# controller.net
KiCad netlist of a schematic drawn in EAGLE
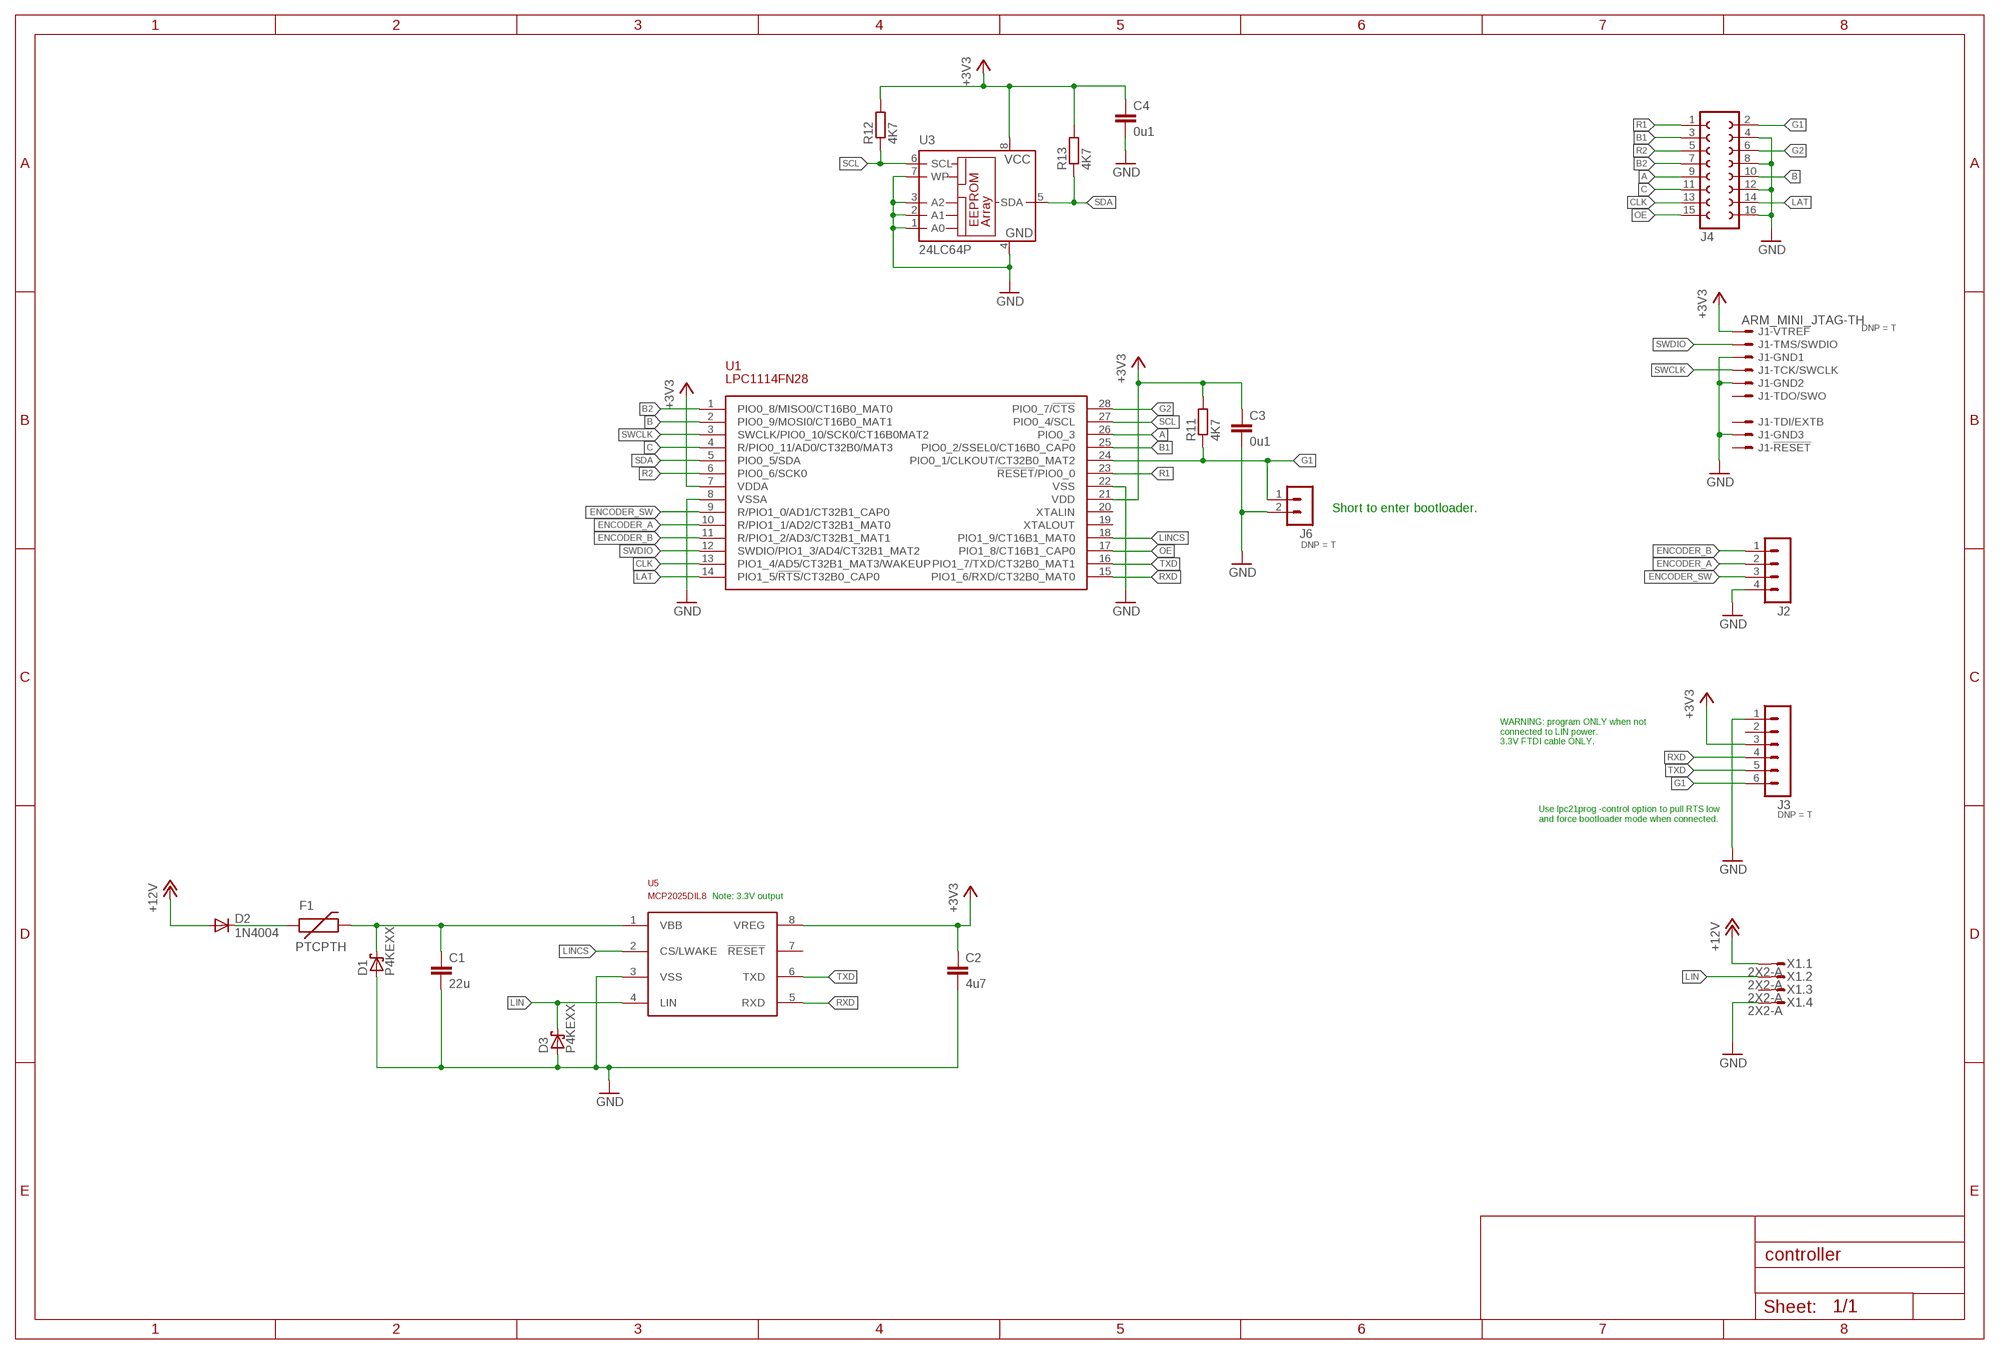
[diagram p0: schematic, sheet 1]

(export (version "E")
  (design (tool "Eeschema 10.0.6"))
  (components
    (comp (ref "C1")
      (value "22u")
      (footprint "eagle-import:C050-024X044")
      (fields (field (name "PARTNO") "FK22X5R1E226M"))
      (libsource (lib "eagle-import") (part "C-EU050-024X044"))
    )
    (comp (ref "C2")
      (value "4u7")
      (footprint "eagle-import:C050-024X044")
      (fields (field (name "PARTNO") "FK28X5R0J475K"))
      (libsource (lib "eagle-import") (part "C-EU050-024X044"))
    )
    (comp (ref "C3")
      (value "0u1")
      (footprint "eagle-import:C050-024X044")
      (fields (field (name "PARTNO") "FK28X7R1H104K"))
      (libsource (lib "eagle-import") (part "C-EU050-024X044"))
    )
    (comp (ref "C4")
      (value "0u1")
      (footprint "eagle-import:C050-024X044")
      (fields (field (name "PARTNO") "FK28X7R1H104K"))
      (libsource (lib "eagle-import") (part "C-EU050-024X044"))
    )
    (comp (ref "D1")
      (value "P4KEXX")
      (footprint "eagle-import:DO41-10")
      (fields (field (name "PARTNO") "P4KE30CA"))
      (libsource (lib "eagle-import") (part "P4KEXX"))
    )
    (comp (ref "D2")
      (value "1N4004")
      (footprint "eagle-import:DO41-10")
      (fields (field (name "PARTNO") "1N4004-TP"))
      (libsource (lib "eagle-import") (part "1N4004"))
    )
    (comp (ref "D3")
      (value "P4KEXX")
      (footprint "eagle-import:DO41-10")
      (fields (field (name "PARTNO") "P4KE30CA"))
      (libsource (lib "eagle-import") (part "P4KEXX"))
    )
    (comp (ref "F1")
      (value "PTCPTH")
      (footprint "eagle-import:PTC")
      (fields (field (name "PARTNO") "CMF-RL10-0"))
      (libsource (lib "eagle-import") (part "PTCPTH"))
    )
    (comp (ref "J1")
      (value "ARM_MINI_JTAG-TH")
      (footprint "eagle-import:FTSH-105-01-XXX-DV")
      (fields (field (name "DNP") "T") (field (name "PARTNO") "*"))
      (libsource (lib "eagle-import") (part "ARM_MINI_JTAG-TH"))
    )
    (comp (ref "J2")
      (value "MA04-1")
      (footprint "eagle-import:MA04-1")
      (fields (field (name "PARTNO") "640454-4"))
      (libsource (lib "eagle-import") (part "MA04-1"))
    )
    (comp (ref "J3")
      (value "MA06-1")
      (footprint "eagle-import:MA06-1")
      (fields (field (name "DNP") "T"))
      (libsource (lib "eagle-import") (part "MA06-1"))
    )
    (comp (ref "J4")
      (value "FE08-2")
      (footprint "eagle-import:FE08-2")
      (fields (field (name "PARTNO") "PPTC082LFBN-RC"))
      (libsource (lib "eagle-import") (part "FE08-2"))
    )
    (comp (ref "J6")
      (value "MA02-1Y")
      (footprint "eagle-import:MA02-1Y")
      (fields (field (name "DNP") "T"))
      (libsource (lib "eagle-import") (part "MA02-1Y"))
    )
    (comp (ref "R11")
      (value "4K7")
      (footprint "eagle-import:0207_10")
      (fields (field (name "PARTNO") "MFR-25FBF52-4K99"))
      (libsource (lib "eagle-import") (part "R-EU_0207/10"))
    )
    (comp (ref "R12")
      (value "4K7")
      (footprint "eagle-import:0207_10")
      (fields (field (name "PARTNO") "MFR-25FBF52-4K99"))
      (libsource (lib "eagle-import") (part "R-EU_0207/10"))
    )
    (comp (ref "R13")
      (value "4K7")
      (footprint "eagle-import:0207_10")
      (fields (field (name "PARTNO") "MFR-25FBF52-4K99"))
      (libsource (lib "eagle-import") (part "R-EU_0207/10"))
    )
    (comp (ref "U1")
      (value "LPC1114FN28")
      (footprint "eagle-import:DIL28")
      (fields (field (name "PARTNO") "LPC1114FN28/102,12"))
      (libsource (lib "eagle-import") (part "LPC1114FN28"))
    )
    (comp (ref "U3")
      (value "24LC64P")
      (footprint "eagle-import:DIL8")
      (fields (field (name "MF") "MICROCHIP") (field (name "MPN") "24LC64-I/P"))
      (libsource (lib "eagle-import") (part "24PLC64"))
    )
    (comp (ref "U5")
      (value "MCP2025DIL8")
      (footprint "eagle-import:DIL8")
      (fields (field (name "PARTNO") "MCP2025-330E/P"))
      (libsource (lib "eagle-import") (part "MCP2025DIL8"))
    )
    (comp (ref "X1")
      (value "2X2-A")
      (footprint "eagle-import:3-794618-4")
      (fields (field (name "PARTNO") "3-794618-4"))
      (libsource (lib "eagle-import") (part "2X2-A"))
    )
  )
  (nets
    (net (code "1") (name "+3V3") (class "Default")
      (node (ref "C2") (pin "1") (pinfunction "1_1") (pintype "passive"))
      (node (ref "C3") (pin "1") (pinfunction "1_1") (pintype "passive"))
      (node (ref "C4") (pin "1") (pinfunction "1_1") (pintype "passive"))
      (node (ref "J1") (pin "1") (pinfunction "S_1") (pintype "passive"))
      (node (ref "J3") (pin "3") (pinfunction "3_3") (pintype "passive"))
      (node (ref "R11") (pin "2") (pinfunction "2_2") (pintype "passive"))
      (node (ref "R12") (pin "2") (pinfunction "2_2") (pintype "passive"))
      (node (ref "R13") (pin "2") (pinfunction "2_2") (pintype "passive"))
      (node (ref "U1") (pin "21") (pinfunction "VDD_21") (pintype "power_in"))
      (node (ref "U1") (pin "7") (pinfunction "VDDA_7") (pintype "power_in"))
      (node (ref "U3") (pin "8") (pinfunction "VCC_8") (pintype "power_in"))
      (node (ref "U5") (pin "8") (pinfunction "VREG_8") (pintype "power_in"))
    )
    (net (code "2") (name "+12V") (class "Default")
      (node (ref "D2") (pin "A") (pinfunction "A_A") (pintype "passive"))
      (node (ref "X1") (pin "1") (pinfunction "S_1") (pintype "passive"))
    )
    (net (code "3") (name "A") (class "Default")
      (node (ref "J4") (pin "9") (pinfunction "9_9") (pintype "passive"))
      (node (ref "U1") (pin "26") (pinfunction "PIO0_3_26") (pintype "bidirectional"))
    )
    (net (code "4") (name "B") (class "Default")
      (node (ref "J4") (pin "10") (pinfunction "10_10") (pintype "passive"))
      (node (ref "U1") (pin "2") (pinfunction "PIO0_9/MOSI0/CT16B0_MAT1_2") (pintype "bidirectional"))
    )
    (net (code "5") (name "B1") (class "Default")
      (node (ref "J4") (pin "3") (pinfunction "3_3") (pintype "passive"))
      (node (ref "U1") (pin "25") (pinfunction "PIO0_2/SSEL0/CT16B0_CAP0_25") (pintype "bidirectional"))
    )
    (net (code "6") (name "B2") (class "Default")
      (node (ref "J4") (pin "7") (pinfunction "7_7") (pintype "passive"))
      (node (ref "U1") (pin "1") (pinfunction "PIO0_8/MISO0/CT16B0_MAT0_1") (pintype "bidirectional"))
    )
    (net (code "7") (name "C") (class "Default")
      (node (ref "J4") (pin "11") (pinfunction "11_11") (pintype "passive"))
      (node (ref "U1") (pin "4") (pinfunction "R/PIO0_11/AD0/CT32B0/MAT3_4") (pintype "bidirectional"))
    )
    (net (code "8") (name "CLK") (class "Default")
      (node (ref "J4") (pin "13") (pinfunction "13_13") (pintype "passive"))
      (node (ref "U1") (pin "13") (pinfunction "PIO1_4/AD5/CT32B1_MAT3/WAKEUP_13") (pintype "bidirectional"))
    )
    (net (code "9") (name "ENCODER_A") (class "Default")
      (node (ref "J2") (pin "2") (pinfunction "2_2") (pintype "passive"))
      (node (ref "U1") (pin "10") (pinfunction "R/PIO1_1/AD2/CT32B1_MAT0_10") (pintype "bidirectional"))
    )
    (net (code "10") (name "ENCODER_B") (class "Default")
      (node (ref "J2") (pin "1") (pinfunction "1_1") (pintype "passive"))
      (node (ref "U1") (pin "11") (pinfunction "R/PIO1_2/AD3/CT32B1_MAT1_11") (pintype "bidirectional"))
    )
    (net (code "11") (name "ENCODER_SW") (class "Default")
      (node (ref "J2") (pin "3") (pinfunction "3_3") (pintype "passive"))
      (node (ref "U1") (pin "9") (pinfunction "R/PIO1_0/AD1/CT32B1_CAP0_9") (pintype "bidirectional"))
    )
    (net (code "12") (name "G1") (class "Default")
      (node (ref "J3") (pin "6") (pinfunction "6_6") (pintype "passive"))
      (node (ref "J4") (pin "2") (pinfunction "2_2") (pintype "passive"))
      (node (ref "J6") (pin "1") (pinfunction "1_1") (pintype "passive"))
      (node (ref "R11") (pin "1") (pinfunction "1_1") (pintype "passive"))
      (node (ref "U1") (pin "24") (pinfunction "PIO0_1/CLKOUT/CT32B0_MAT2_24") (pintype "bidirectional"))
    )
    (net (code "13") (name "G2") (class "Default")
      (node (ref "J4") (pin "6") (pinfunction "6_6") (pintype "passive"))
      (node (ref "U1") (pin "28") (pinfunction "PIO0_7/~{CTS}_28") (pintype "bidirectional"))
    )
    (net (code "14") (name "GND") (class "Default")
      (node (ref "C1") (pin "2") (pinfunction "2_2") (pintype "passive"))
      (node (ref "C2") (pin "2") (pinfunction "2_2") (pintype "passive"))
      (node (ref "C3") (pin "2") (pinfunction "2_2") (pintype "passive"))
      (node (ref "C4") (pin "2") (pinfunction "2_2") (pintype "passive"))
      (node (ref "D1") (pin "A") (pinfunction "A_A") (pintype "passive"))
      (node (ref "D3") (pin "A") (pinfunction "A_A") (pintype "passive"))
      (node (ref "J1") (pin "3") (pinfunction "S_3") (pintype "passive"))
      (node (ref "J1") (pin "5") (pinfunction "S_5") (pintype "passive"))
      (node (ref "J1") (pin "9") (pinfunction "S_9") (pintype "passive"))
      (node (ref "J2") (pin "4") (pinfunction "4_4") (pintype "passive"))
      (node (ref "J3") (pin "1") (pinfunction "1_1") (pintype "passive"))
      (node (ref "J4") (pin "12") (pinfunction "12_12") (pintype "passive"))
      (node (ref "J4") (pin "16") (pinfunction "16_16") (pintype "passive"))
      (node (ref "J4") (pin "4") (pinfunction "4_4") (pintype "passive"))
      (node (ref "J4") (pin "8") (pinfunction "8_8") (pintype "passive"))
      (node (ref "J6") (pin "2") (pinfunction "2_2") (pintype "passive"))
      (node (ref "U1") (pin "22") (pinfunction "VSS_22") (pintype "power_in"))
      (node (ref "U1") (pin "8") (pinfunction "VSSA_8") (pintype "power_in"))
      (node (ref "U3") (pin "1") (pinfunction "A0_1") (pintype "input"))
      (node (ref "U3") (pin "2") (pinfunction "A1_2") (pintype "input"))
      (node (ref "U3") (pin "3") (pinfunction "A2_3") (pintype "input"))
      (node (ref "U3") (pin "4") (pinfunction "GND_4") (pintype "power_in"))
      (node (ref "U3") (pin "7") (pinfunction "WP_7") (pintype "input"))
      (node (ref "U5") (pin "3") (pinfunction "VSS_3") (pintype "power_in"))
      (node (ref "X1") (pin "4") (pinfunction "S_4") (pintype "passive"))
    )
    (net (code "15") (name "LAT") (class "Default")
      (node (ref "J4") (pin "14") (pinfunction "14_14") (pintype "passive"))
      (node (ref "U1") (pin "14") (pinfunction "PIO1_5/~{RTS}/CT32B0_CAP0_14") (pintype "bidirectional"))
    )
    (net (code "16") (name "LIN") (class "Default")
      (node (ref "D3") (pin "C") (pinfunction "C_C") (pintype "passive"))
      (node (ref "U5") (pin "4") (pinfunction "LIN_4") (pintype "bidirectional"))
      (node (ref "X1") (pin "2") (pinfunction "S_2") (pintype "passive"))
    )
    (net (code "17") (name "LINCS") (class "Default")
      (node (ref "U1") (pin "18") (pinfunction "PIO1_9/CT16B1_MAT0_18") (pintype "bidirectional"))
      (node (ref "U5") (pin "2") (pinfunction "CS/LWAKE_2") (pintype "input"))
    )
    (net (code "18") (name "Net-(F1-1)") (class "Default")
      (node (ref "D2") (pin "C") (pinfunction "C_C") (pintype "passive"))
      (node (ref "F1") (pin "P$1") (pinfunction "1_P$1") (pintype "bidirectional"))
    )
    (net (code "19") (name "Net-(F1-2)") (class "Default")
      (node (ref "C1") (pin "1") (pinfunction "1_1") (pintype "passive"))
      (node (ref "D1") (pin "C") (pinfunction "C_C") (pintype "passive"))
      (node (ref "F1") (pin "P$2") (pinfunction "2_P$2") (pintype "bidirectional"))
      (node (ref "U5") (pin "1") (pinfunction "VBB_1") (pintype "power_in"))
    )
    (net (code "20") (name "OE") (class "Default")
      (node (ref "J4") (pin "15") (pinfunction "15_15") (pintype "passive"))
      (node (ref "U1") (pin "17") (pinfunction "PIO1_8/CT16B1_CAP0_17") (pintype "bidirectional"))
    )
    (net (code "21") (name "R1") (class "Default")
      (node (ref "J4") (pin "1") (pinfunction "1_1") (pintype "passive"))
      (node (ref "U1") (pin "23") (pinfunction "~{RESET}/PIO0_0_23") (pintype "bidirectional"))
    )
    (net (code "22") (name "R2") (class "Default")
      (node (ref "J4") (pin "5") (pinfunction "5_5") (pintype "passive"))
      (node (ref "U1") (pin "6") (pinfunction "PIO0_6/SCK0_6") (pintype "bidirectional"))
    )
    (net (code "23") (name "RXD") (class "Default")
      (node (ref "J3") (pin "4") (pinfunction "4_4") (pintype "passive"))
      (node (ref "U1") (pin "15") (pinfunction "PIO1_6/RXD/CT32B0_MAT0_15") (pintype "bidirectional"))
      (node (ref "U5") (pin "5") (pinfunction "RXD_5") (pintype "output"))
    )
    (net (code "24") (name "SCL") (class "Default")
      (node (ref "R12") (pin "1") (pinfunction "1_1") (pintype "passive"))
      (node (ref "U1") (pin "27") (pinfunction "PIO0_4/SCL_27") (pintype "bidirectional"))
      (node (ref "U3") (pin "6") (pinfunction "SCL_6") (pintype "input"))
    )
    (net (code "25") (name "SDA") (class "Default")
      (node (ref "R13") (pin "1") (pinfunction "1_1") (pintype "passive"))
      (node (ref "U1") (pin "5") (pinfunction "PIO0_5/SDA_5") (pintype "bidirectional"))
      (node (ref "U3") (pin "5") (pinfunction "SDA_5") (pintype "bidirectional"))
    )
    (net (code "26") (name "SWCLK") (class "Default")
      (node (ref "J1") (pin "4") (pinfunction "S_4") (pintype "passive"))
      (node (ref "U1") (pin "3") (pinfunction "SWCLK/PIO0_10/SCK0/CT16B0MAT2_3") (pintype "bidirectional"))
    )
    (net (code "27") (name "SWDIO") (class "Default")
      (node (ref "J1") (pin "2") (pinfunction "S_2") (pintype "passive"))
      (node (ref "U1") (pin "12") (pinfunction "SWDIO/PIO1_3/AD4/CT32B1_MAT2_12") (pintype "bidirectional"))
    )
    (net (code "28") (name "TXD") (class "Default")
      (node (ref "J3") (pin "5") (pinfunction "5_5") (pintype "passive"))
      (node (ref "U1") (pin "16") (pinfunction "PIO1_7/TXD/CT32B0_MAT1_16") (pintype "bidirectional"))
      (node (ref "U5") (pin "6") (pinfunction "TXD_6") (pintype "input"))
    )
    (net (code "29") (name "unconnected-(J1A-S-Pad10)") (class "Default")
      (node (ref "J1") (pin "10") (pinfunction "S_10") (pintype "passive"))
    )
    (net (code "30") (name "unconnected-(J1F-S-Pad8)") (class "Default")
      (node (ref "J1") (pin "8") (pinfunction "S_8") (pintype "passive"))
    )
    (net (code "31") (name "unconnected-(J1G-S-Pad6)") (class "Default")
      (node (ref "J1") (pin "6") (pinfunction "S_6") (pintype "passive"))
    )
    (net (code "32") (name "unconnected-(J3-Pad2)") (class "Default")
      (node (ref "J3") (pin "2") (pinfunction "2_2") (pintype "passive"))
    )
    (net (code "33") (name "unconnected-(U1-XTALIN-Pad20)") (class "Default")
      (node (ref "U1") (pin "20") (pinfunction "XTALIN_20") (pintype "input"))
    )
    (net (code "34") (name "unconnected-(U1-XTALOUT-Pad19)") (class "Default")
      (node (ref "U1") (pin "19") (pinfunction "XTALOUT_19") (pintype "output"))
    )
    (net (code "35") (name "unconnected-(U5-~{RESET}-Pad7)") (class "Default")
      (node (ref "U5") (pin "7") (pinfunction "~{RESET}_7") (pintype "open_collector"))
    )
    (net (code "36") (name "unconnected-(X1C-S-Pad3)") (class "Default")
      (node (ref "X1") (pin "3") (pinfunction "S_3") (pintype "passive"))
    )
  )
)
